# TPA6139A2.net
KiCad netlist of a schematic drawn in EAGLE
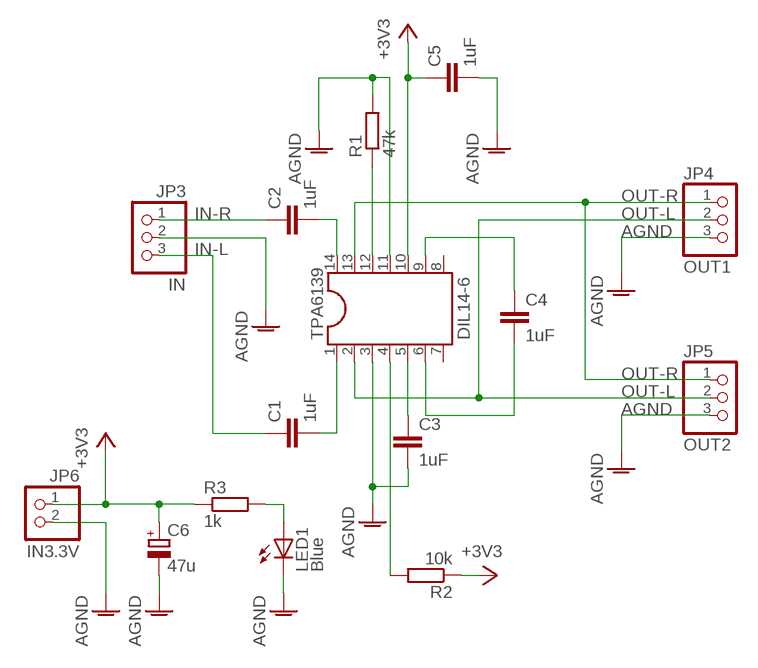
[diagram p0: schematic, sheet 1]

(export (version "E")
  (design (tool "Eeschema 10.0.6"))
  (components
    (comp (ref "C1")
      (value "1uF")
      (footprint "eagle-import:C050-050X075")
      (libsource (lib "eagle-import") (part "C-EU050-050X075"))
    )
    (comp (ref "C2")
      (value "1uF")
      (footprint "eagle-import:C050-050X075")
      (libsource (lib "eagle-import") (part "C-EU050-050X075"))
    )
    (comp (ref "C3")
      (value "1uF")
      (footprint "eagle-import:C050-024X044")
      (libsource (lib "eagle-import") (part "C-EU050-024X044"))
    )
    (comp (ref "C4")
      (value "1uF")
      (footprint "eagle-import:C050-024X044")
      (libsource (lib "eagle-import") (part "C-EU050-024X044"))
    )
    (comp (ref "C5")
      (value "1uF")
      (footprint "eagle-import:C050-024X044")
      (libsource (lib "eagle-import") (part "C-EU050-024X044"))
    )
    (comp (ref "C6")
      (value "47u")
      (footprint "eagle-import:TT2D5L")
      (libsource (lib "eagle-import") (part "CPOL-EUTT2D5L"))
    )
    (comp (ref "JP3")
      (value "IN")
      (footprint "eagle-import:1X03")
      (libsource (lib "eagle-import") (part "PINHD-1X3"))
    )
    (comp (ref "JP4")
      (value "OUT1")
      (footprint "eagle-import:1X03")
      (libsource (lib "eagle-import") (part "PINHD-1X3"))
    )
    (comp (ref "JP5")
      (value "OUT2")
      (footprint "eagle-import:1X03")
      (libsource (lib "eagle-import") (part "PINHD-1X3"))
    )
    (comp (ref "JP6")
      (value "IN3.3V")
      (footprint "eagle-import:1X02")
      (libsource (lib "eagle-import") (part "PINHD-1X2"))
    )
    (comp (ref "LED1")
      (value "Blue")
      (footprint "eagle-import:LED3MM")
      (libsource (lib "eagle-import") (part "LED3MM"))
    )
    (comp (ref "R1")
      (value "47k")
      (footprint "eagle-import:0207_7")
      (libsource (lib "eagle-import") (part "R-EU_0207/7"))
    )
    (comp (ref "R2")
      (value "10k")
      (footprint "eagle-import:0207_7")
      (libsource (lib "eagle-import") (part "R-EU_0207/7"))
    )
    (comp (ref "R3")
      (value "1k")
      (footprint "eagle-import:0207_7")
      (libsource (lib "eagle-import") (part "R-EU_0207/7"))
    )
    (comp (ref "TPA6139")
      (value "DIL14-6")
      (footprint "eagle-import:DIL14-6")
      (libsource (lib "eagle-import") (part "DIL14-6"))
    )
  )
  (nets
    (net (code "1") (name "+3V3") (class "Default")
      (node (ref "C5") (pin "1") (pinfunction "1_1") (pintype "passive"))
      (node (ref "C6") (pin "+") (pinfunction "+_+") (pintype "passive"))
      (node (ref "JP6") (pin "1") (pinfunction "1_1") (pintype "passive"))
      (node (ref "R2") (pin "1") (pinfunction "1_1") (pintype "passive"))
      (node (ref "R3") (pin "1") (pinfunction "1_1") (pintype "passive"))
      (node (ref "TPA6139") (pin "10") (pinfunction "10_10") (pintype "passive"))
    )
    (net (code "2") (name "/IN-L") (class "Default")
      (node (ref "C1") (pin "1") (pinfunction "1_1") (pintype "passive"))
      (node (ref "JP3") (pin "3") (pinfunction "3_3") (pintype "passive"))
    )
    (net (code "3") (name "/IN-R") (class "Default")
      (node (ref "C2") (pin "1") (pinfunction "1_1") (pintype "passive"))
      (node (ref "JP3") (pin "1") (pinfunction "1_1") (pintype "passive"))
    )
    (net (code "4") (name "/OUT-L") (class "Default")
      (node (ref "JP4") (pin "2") (pinfunction "2_2") (pintype "passive"))
      (node (ref "JP5") (pin "2") (pinfunction "2_2") (pintype "passive"))
      (node (ref "TPA6139") (pin "2") (pinfunction "2_2") (pintype "passive"))
    )
    (net (code "5") (name "/OUT-R") (class "Default")
      (node (ref "JP4") (pin "1") (pinfunction "1_1") (pintype "passive"))
      (node (ref "JP5") (pin "1") (pinfunction "1_1") (pintype "passive"))
      (node (ref "TPA6139") (pin "13") (pinfunction "13_13") (pintype "passive"))
    )
    (net (code "6") (name "AGND") (class "Default")
      (node (ref "C3") (pin "2") (pinfunction "2_2") (pintype "passive"))
      (node (ref "C5") (pin "2") (pinfunction "2_2") (pintype "passive"))
      (node (ref "C6") (pin "-") (pinfunction "-_-") (pintype "passive"))
      (node (ref "JP3") (pin "2") (pinfunction "2_2") (pintype "passive"))
      (node (ref "JP4") (pin "3") (pinfunction "3_3") (pintype "passive"))
      (node (ref "JP5") (pin "3") (pinfunction "3_3") (pintype "passive"))
      (node (ref "JP6") (pin "2") (pinfunction "2_2") (pintype "passive"))
      (node (ref "LED1") (pin "K") (pinfunction "C_K") (pintype "passive"))
      (node (ref "R1") (pin "2") (pinfunction "2_2") (pintype "passive"))
      (node (ref "TPA6139") (pin "11") (pinfunction "11_11") (pintype "passive"))
      (node (ref "TPA6139") (pin "3") (pinfunction "3_3") (pintype "passive"))
    )
    (net (code "7") (name "Net-(C1-Pad2)") (class "Default")
      (node (ref "C1") (pin "2") (pinfunction "2_2") (pintype "passive"))
      (node (ref "TPA6139") (pin "1") (pinfunction "1_1") (pintype "passive"))
    )
    (net (code "8") (name "Net-(C2-Pad2)") (class "Default")
      (node (ref "C2") (pin "2") (pinfunction "2_2") (pintype "passive"))
      (node (ref "TPA6139") (pin "14") (pinfunction "14_14") (pintype "passive"))
    )
    (net (code "9") (name "Net-(C3-Pad1)") (class "Default")
      (node (ref "C3") (pin "1") (pinfunction "1_1") (pintype "passive"))
      (node (ref "TPA6139") (pin "5") (pinfunction "5_5") (pintype "passive"))
    )
    (net (code "10") (name "Net-(C4-Pad1)") (class "Default")
      (node (ref "C4") (pin "1") (pinfunction "1_1") (pintype "passive"))
      (node (ref "TPA6139") (pin "9") (pinfunction "9_9") (pintype "passive"))
    )
    (net (code "11") (name "Net-(C4-Pad2)") (class "Default")
      (node (ref "C4") (pin "2") (pinfunction "2_2") (pintype "passive"))
      (node (ref "TPA6139") (pin "6") (pinfunction "6_6") (pintype "passive"))
    )
    (net (code "12") (name "Net-(LED1-PadA)") (class "Default")
      (node (ref "LED1") (pin "A") (pinfunction "A_A") (pintype "passive"))
      (node (ref "R3") (pin "2") (pinfunction "2_2") (pintype "passive"))
    )
    (net (code "13") (name "Net-(R1-Pad1)") (class "Default")
      (node (ref "R1") (pin "1") (pinfunction "1_1") (pintype "passive"))
      (node (ref "TPA6139") (pin "12") (pinfunction "12_12") (pintype "passive"))
    )
    (net (code "14") (name "Net-(R2-Pad2)") (class "Default")
      (node (ref "R2") (pin "2") (pinfunction "2_2") (pintype "passive"))
      (node (ref "TPA6139") (pin "4") (pinfunction "4_4") (pintype "passive"))
    )
    (net (code "15") (name "unconnected-(TPA6139-Pad7)") (class "Default")
      (node (ref "TPA6139") (pin "7") (pinfunction "7_7") (pintype "passive"))
    )
    (net (code "16") (name "unconnected-(TPA6139-Pad8)") (class "Default")
      (node (ref "TPA6139") (pin "8") (pinfunction "8_8") (pintype "passive"))
    )
  )
)
